# Omnitouch.net
KiCad netlist of a schematic drawn in EasyEDA
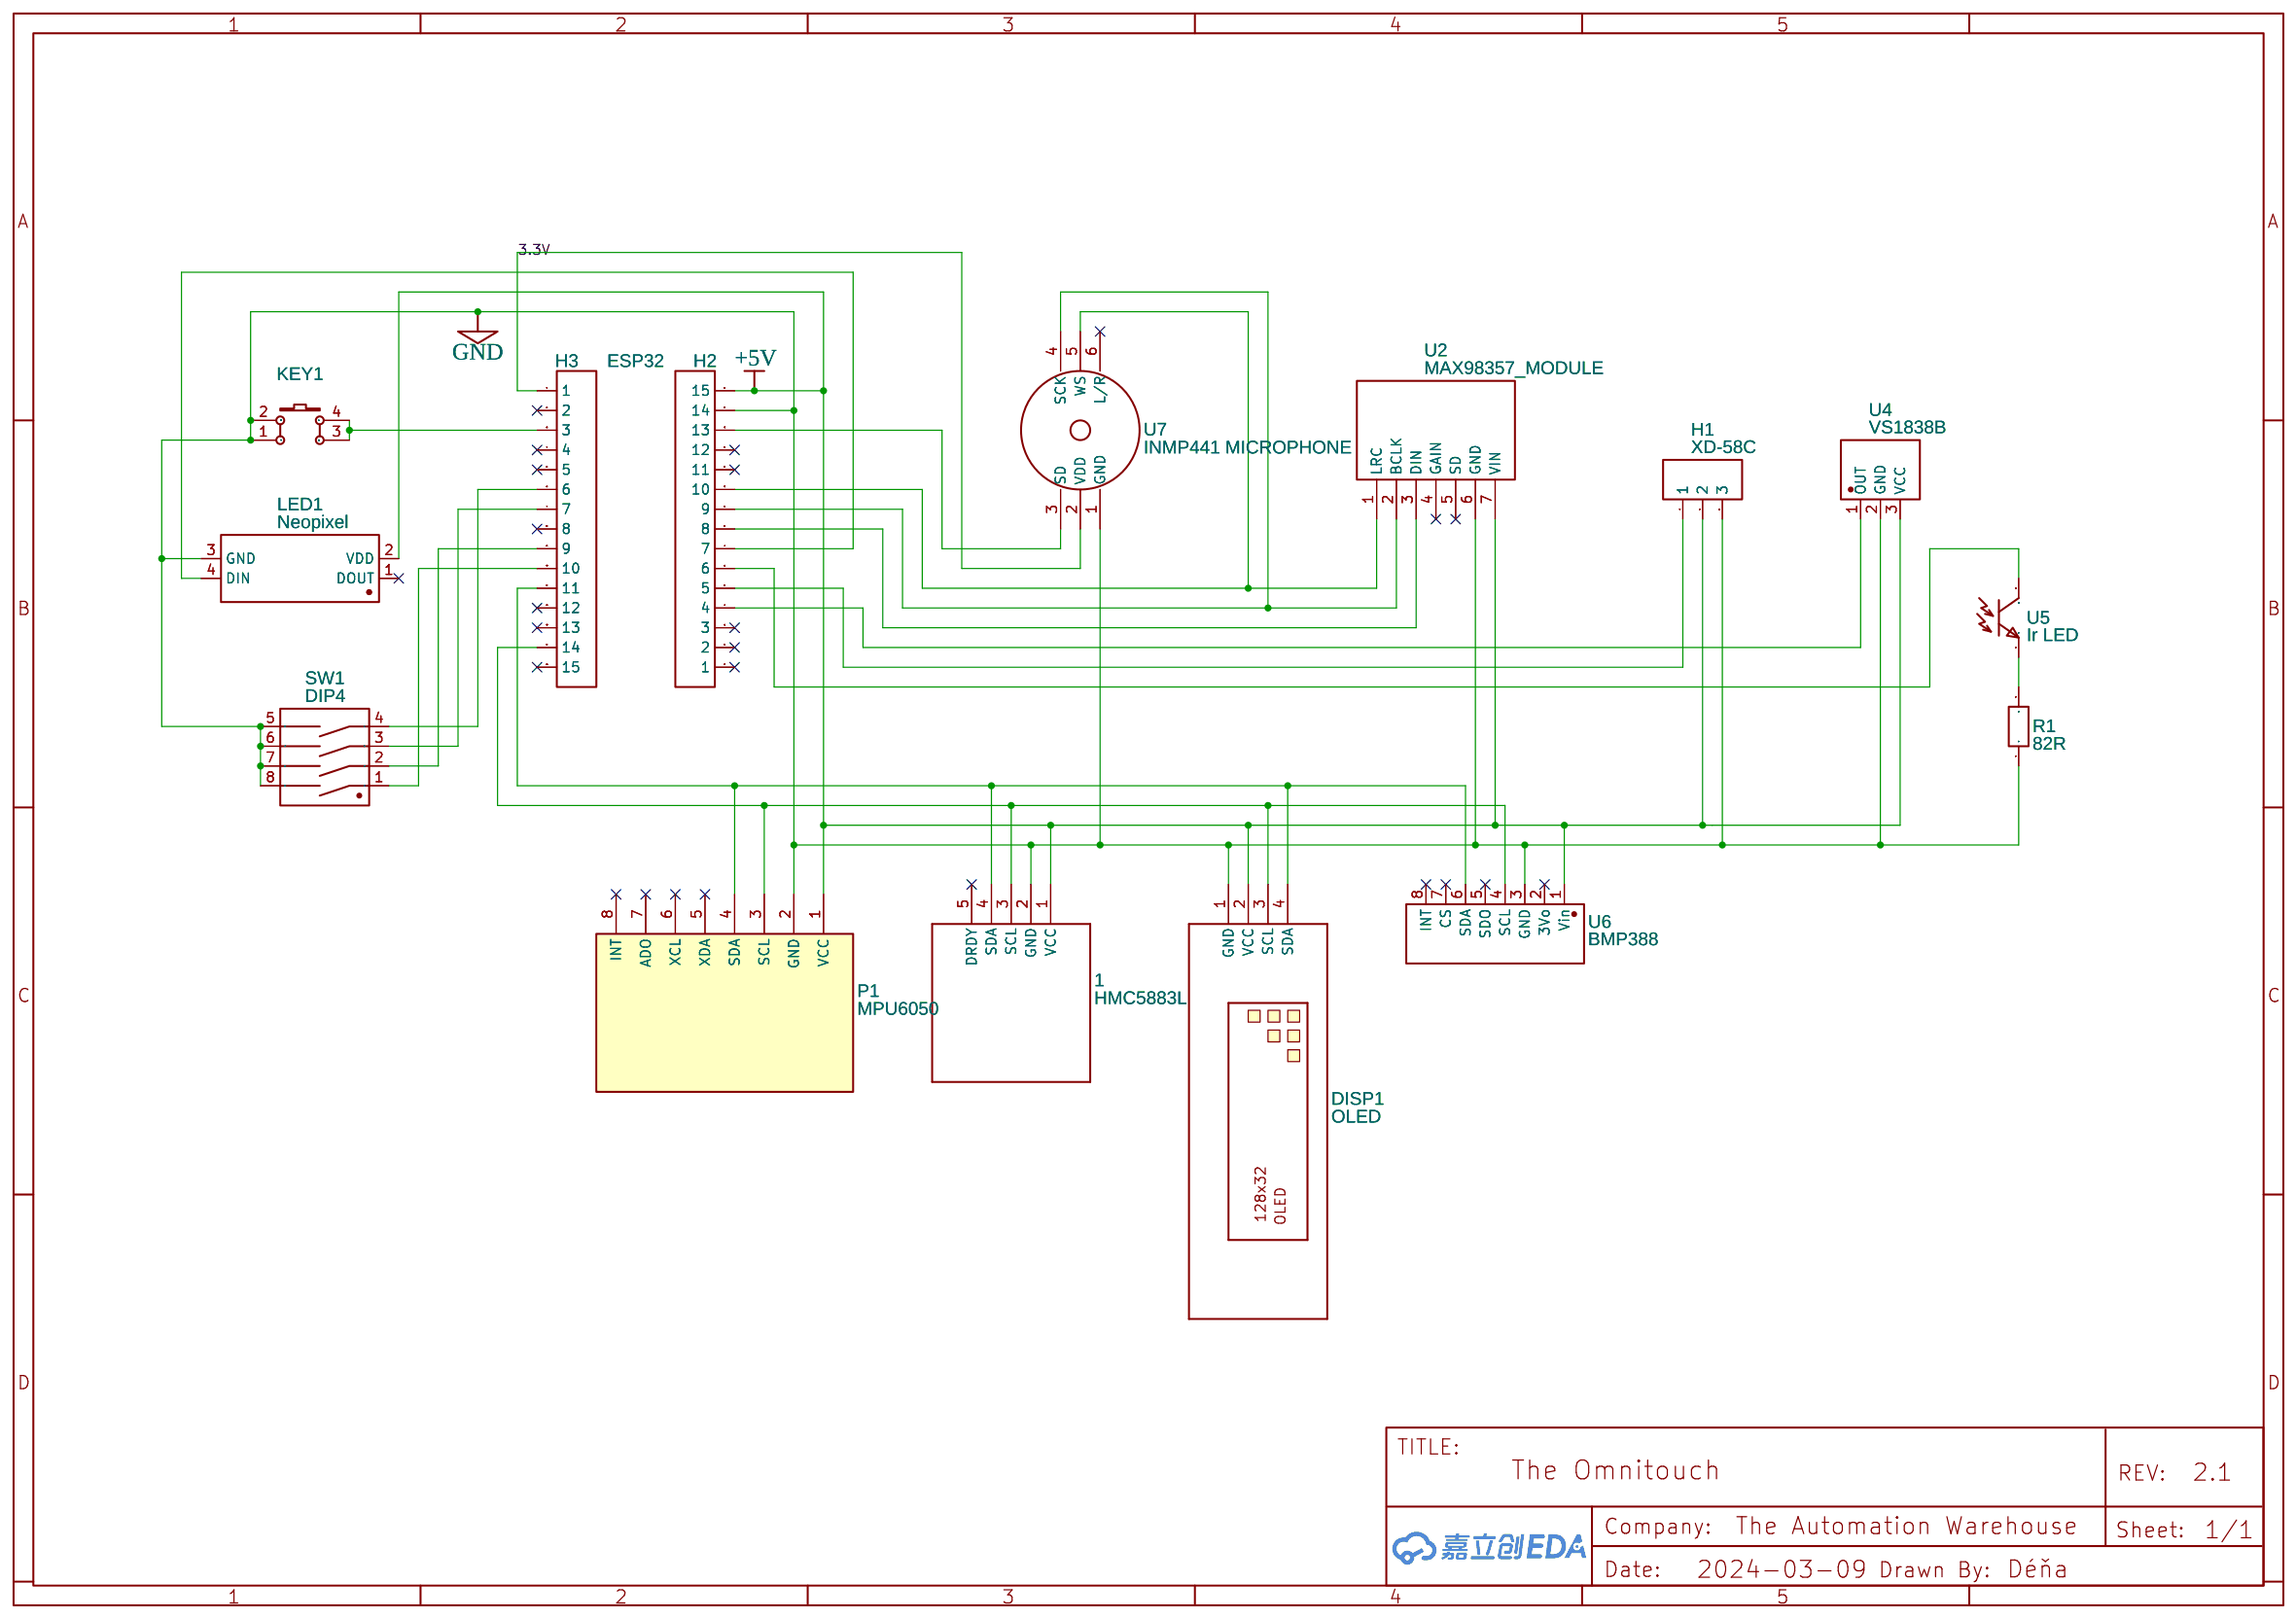
[diagram p0: schematic sheet]

(export (version "E")
  (design (tool "Eeschema 10.0.6"))
  (components
    (comp (ref "1") (value "HMC5883L") (libsource (lib "") (part "COMPASS-HMC5883L")))
    (comp (ref "DISP1") (value "OLED") (libsource (lib "") (part "DISPLAY-OLED-128X32")))
    (comp (ref "H1")
      (value "XD-58C")
      (fields (field (name "BOM_Supplier Part") "C146690"))
      (libsource (lib "") (part "HDR-F-2.54_1x3"))
    )
    (comp (ref "H2")
      (value "HDR-F-2.54_1x15")
      (fields (field (name "BOM_Supplier Part") "C124408"))
      (libsource (lib "") (part "HDR-F-2.54_1x15_1"))
    )
    (comp (ref "H3")
      (value "ESP32")
      (fields (field (name "BOM_Supplier Part") "C124408"))
      (libsource (lib "") (part "HDR-F-2.54_1x15"))
    )
    (comp (ref "KEY1")
      (value "K4-6×6_TH")
      (fields
        (field (name "BOM_Manufacturer Part") "K2-1102DP-E4SW-04")
        (field (name "BOM_Supplier Part") "C136684")
      )
      (libsource (lib "") (part "K4-6×6_TH"))
    )
    (comp (ref "LED1")
      (value "Neopixel")
      (fields (field (name "Manufacturer Part") "WS2812D-F8") (field (name "Manufacturer") "worldsemi"))
      (libsource (lib "") (part "WS2812D-F8"))
    )
    (comp (ref "P1") (value "MPU6050") (libsource (lib "") (part "MPU6050")))
    (comp (ref "R1") (value "82R") (libsource (lib "") (part "R_AXIAL-0.4_EU")))
    (comp (ref "SW1")
      (value "DIP4")
      (fields
        (field (name "Manufacturer Part") "KF1001-04P-R0-GL-DFT-01B")
        (field (name "Manufacturer") "凯峰")
      )
      (libsource (lib "") (part "KF1001-04P-R0-GL-DFT-01B"))
    )
    (comp (ref "U2")
      (value "MAX98357_MODULE")
      (fields (field (name "BOM_Manufacturer Part") "MAX98357"))
      (libsource (lib "") (part "MAX98357_MODULE"))
    )
    (comp (ref "U4") (value "VS1838B") (libsource (lib "") (part "VS1838B")))
    (comp (ref "U5")
      (value "Ir LED")
      (fields
        (field (name "Manufacturer Part") "PT334-6B(BY)(K)")
        (field (name "Manufacturer") "EVERLIGHT(亿光)")
      )
      (libsource (lib "") (part "PT334-6B(BY)(K)"))
    )
    (comp (ref "U6") (value "BMP388") (libsource (lib "") (part "Adafruit BMP388")))
    (comp (ref "U7") (value "INMP441 MICROPHONE") (libsource (lib "") (part "INMP441 MICROPHONE")))
  )
  (nets
    (net (code "1") (name "+5V") (class "Default")
      (node (ref "1") (pin "1") (pinfunction "VCC_1") (pintype "bidirectional"))
      (node (ref "DISP1") (pin "2") (pinfunction "VCC_2") (pintype "bidirectional"))
      (node (ref "H1") (pin "2") (pinfunction "2_2") (pintype "input"))
      (node (ref "H2") (pin "15") (pinfunction "15_15") (pintype "unspecified"))
      (node (ref "LED1") (pin "2") (pinfunction "VDD_2") (pintype "unspecified"))
      (node (ref "P1") (pin "1") (pinfunction "VCC_1") (pintype "unspecified"))
      (node (ref "U2") (pin "7") (pinfunction "VIN_7") (pintype "unspecified"))
      (node (ref "U4") (pin "3") (pinfunction "VCC_3") (pintype "unspecified"))
      (node (ref "U6") (pin "1") (pinfunction "Vin_1") (pintype "unspecified"))
    )
    (net (code "2") (name "/3.3V") (class "Default")
      (node (ref "H3") (pin "1") (pinfunction "1_1") (pintype "unspecified"))
      (node (ref "U7") (pin "2") (pinfunction "VDD_2") (pintype "unspecified"))
    )
    (net (code "3") (name "GND") (class "Default")
      (node (ref "1") (pin "2") (pinfunction "GND_2") (pintype "bidirectional"))
      (node (ref "DISP1") (pin "1") (pinfunction "GND_1") (pintype "bidirectional"))
      (node (ref "H1") (pin "3") (pinfunction "3_3") (pintype "input"))
      (node (ref "H2") (pin "14") (pinfunction "14_14") (pintype "unspecified"))
      (node (ref "KEY1") (pin "1") (pinfunction "1_1") (pintype "unspecified"))
      (node (ref "KEY1") (pin "2") (pinfunction "2_2") (pintype "unspecified"))
      (node (ref "LED1") (pin "3") (pinfunction "GND_3") (pintype "unspecified"))
      (node (ref "P1") (pin "2") (pinfunction "GND_2") (pintype "unspecified"))
      (node (ref "R1") (pin "1") (pinfunction "1_1") (pintype "unspecified"))
      (node (ref "SW1") (pin "5") (pinfunction "6_5") (pintype "unspecified"))
      (node (ref "SW1") (pin "6") (pinfunction "7_6") (pintype "unspecified"))
      (node (ref "SW1") (pin "7") (pinfunction "8_7") (pintype "unspecified"))
      (node (ref "SW1") (pin "8") (pinfunction "9_8") (pintype "unspecified"))
      (node (ref "U2") (pin "6") (pinfunction "GND_6") (pintype "unspecified"))
      (node (ref "U4") (pin "2") (pinfunction "GND_2") (pintype "unspecified"))
      (node (ref "U6") (pin "3") (pinfunction "GND_3") (pintype "unspecified"))
      (node (ref "U7") (pin "1") (pinfunction "GND_1") (pintype "unspecified"))
    )
    (net (code "4") (name "Net-(1-SCL)") (class "Default")
      (node (ref "1") (pin "3") (pinfunction "SCL_3") (pintype "bidirectional"))
      (node (ref "DISP1") (pin "3") (pinfunction "SCL_3") (pintype "bidirectional"))
      (node (ref "H3") (pin "14") (pinfunction "14_14") (pintype "unspecified"))
      (node (ref "P1") (pin "3") (pinfunction "SCL_3") (pintype "unspecified"))
      (node (ref "U6") (pin "4") (pinfunction "SCL_4") (pintype "unspecified"))
    )
    (net (code "5") (name "Net-(1-SDA)") (class "Default")
      (node (ref "1") (pin "4") (pinfunction "SDA_4") (pintype "bidirectional"))
      (node (ref "DISP1") (pin "4") (pinfunction "SDA_4") (pintype "bidirectional"))
      (node (ref "H3") (pin "11") (pinfunction "11_11") (pintype "unspecified"))
      (node (ref "P1") (pin "4") (pinfunction "SDA_4") (pintype "unspecified"))
      (node (ref "U6") (pin "6") (pinfunction "SDA_6") (pintype "unspecified"))
    )
    (net (code "6") (name "Net-(H1-Pad1)") (class "Default")
      (node (ref "H1") (pin "1") (pinfunction "1_1") (pintype "input"))
      (node (ref "H2") (pin "5") (pinfunction "5_5") (pintype "unspecified"))
    )
    (net (code "7") (name "Net-(H3-Pad3)") (class "Default")
      (node (ref "H3") (pin "3") (pinfunction "3_3") (pintype "unspecified"))
      (node (ref "KEY1") (pin "3") (pinfunction "3_3") (pintype "unspecified"))
      (node (ref "KEY1") (pin "4") (pinfunction "4_4") (pintype "unspecified"))
    )
    (net (code "8") (name "Net-(H3-Pad6)") (class "Default")
      (node (ref "H3") (pin "6") (pinfunction "6_6") (pintype "unspecified"))
      (node (ref "SW1") (pin "4") (pinfunction "4_4") (pintype "unspecified"))
    )
    (net (code "9") (name "Net-(H3-Pad7)") (class "Default")
      (node (ref "H3") (pin "7") (pinfunction "7_7") (pintype "unspecified"))
      (node (ref "SW1") (pin "3") (pinfunction "3_3") (pintype "unspecified"))
    )
    (net (code "10") (name "Net-(H3-Pad9)") (class "Default")
      (node (ref "H3") (pin "9") (pinfunction "9_9") (pintype "unspecified"))
      (node (ref "SW1") (pin "2") (pinfunction "2_2") (pintype "unspecified"))
    )
    (net (code "11") (name "Net-(H3-Pad10)") (class "Default")
      (node (ref "H3") (pin "10") (pinfunction "10_10") (pintype "unspecified"))
      (node (ref "SW1") (pin "1") (pinfunction "1_1") (pintype "unspecified"))
    )
    (net (code "12") (name "Net-(LED1-DIN)") (class "Default")
      (node (ref "H2") (pin "7") (pinfunction "7_7") (pintype "unspecified"))
      (node (ref "LED1") (pin "4") (pinfunction "DIN_4") (pintype "unspecified"))
    )
    (net (code "13") (name "Net-(U2-BCLK)") (class "Default")
      (node (ref "H2") (pin "9") (pinfunction "9_9") (pintype "unspecified"))
      (node (ref "U2") (pin "2") (pinfunction "BCLK_2") (pintype "unspecified"))
      (node (ref "U7") (pin "4") (pinfunction "SCK_4") (pintype "unspecified"))
    )
    (net (code "14") (name "Net-(U2-DIN)") (class "Default")
      (node (ref "H2") (pin "8") (pinfunction "8_8") (pintype "unspecified"))
      (node (ref "U2") (pin "3") (pinfunction "DIN_3") (pintype "unspecified"))
    )
    (net (code "15") (name "Net-(U2-LRC)") (class "Default")
      (node (ref "H2") (pin "10") (pinfunction "10_10") (pintype "unspecified"))
      (node (ref "U2") (pin "1") (pinfunction "LRC_1") (pintype "unspecified"))
      (node (ref "U7") (pin "5") (pinfunction "WS_5") (pintype "unspecified"))
    )
    (net (code "16") (name "Net-(U4-OUT)") (class "Default")
      (node (ref "H2") (pin "4") (pinfunction "4_4") (pintype "unspecified"))
      (node (ref "U4") (pin "1") (pinfunction "OUT_1") (pintype "unspecified"))
    )
    (net (code "17") (name "Net-(U5-C)") (class "Default")
      (node (ref "H2") (pin "6") (pinfunction "6_6") (pintype "unspecified"))
      (node (ref "U5") (pin "2") (pinfunction "C_2") (pintype "unspecified"))
    )
    (net (code "18") (name "Net-(U5-E)") (class "Default")
      (node (ref "R1") (pin "2") (pinfunction "2_2") (pintype "unspecified"))
      (node (ref "U5") (pin "1") (pinfunction "E_1") (pintype "unspecified"))
    )
    (net (code "19") (name "Net-(U7-SD)") (class "Default")
      (node (ref "H2") (pin "13") (pinfunction "13_13") (pintype "unspecified"))
      (node (ref "U7") (pin "3") (pinfunction "SD_3") (pintype "unspecified"))
    )
    (net (code "20") (name "unconnected-(1-DRDY-Pad5)") (class "Default")
      (node (ref "1") (pin "5") (pinfunction "DRDY_5") (pintype "bidirectional+no_connect"))
    )
    (net (code "21") (name "unconnected-(H2-Pad1)") (class "Default")
      (node (ref "H2") (pin "1") (pinfunction "1_1") (pintype "unspecified+no_connect"))
    )
    (net (code "22") (name "unconnected-(H2-Pad2)") (class "Default")
      (node (ref "H2") (pin "2") (pinfunction "2_2") (pintype "unspecified+no_connect"))
    )
    (net (code "23") (name "unconnected-(H2-Pad3)") (class "Default")
      (node (ref "H2") (pin "3") (pinfunction "3_3") (pintype "unspecified+no_connect"))
    )
    (net (code "24") (name "unconnected-(H2-Pad11)") (class "Default")
      (node (ref "H2") (pin "11") (pinfunction "11_11") (pintype "unspecified+no_connect"))
    )
    (net (code "25") (name "unconnected-(H2-Pad12)") (class "Default")
      (node (ref "H2") (pin "12") (pinfunction "12_12") (pintype "unspecified+no_connect"))
    )
    (net (code "26") (name "unconnected-(H3-Pad2)") (class "Default")
      (node (ref "H3") (pin "2") (pinfunction "2_2") (pintype "unspecified+no_connect"))
    )
    (net (code "27") (name "unconnected-(H3-Pad4)") (class "Default")
      (node (ref "H3") (pin "4") (pinfunction "4_4") (pintype "unspecified+no_connect"))
    )
    (net (code "28") (name "unconnected-(H3-Pad5)") (class "Default")
      (node (ref "H3") (pin "5") (pinfunction "5_5") (pintype "unspecified+no_connect"))
    )
    (net (code "29") (name "unconnected-(H3-Pad8)") (class "Default")
      (node (ref "H3") (pin "8") (pinfunction "8_8") (pintype "unspecified+no_connect"))
    )
    (net (code "30") (name "unconnected-(H3-Pad12)") (class "Default")
      (node (ref "H3") (pin "12") (pinfunction "12_12") (pintype "unspecified+no_connect"))
    )
    (net (code "31") (name "unconnected-(H3-Pad13)") (class "Default")
      (node (ref "H3") (pin "13") (pinfunction "13_13") (pintype "unspecified+no_connect"))
    )
    (net (code "32") (name "unconnected-(H3-Pad15)") (class "Default")
      (node (ref "H3") (pin "15") (pinfunction "15_15") (pintype "unspecified+no_connect"))
    )
    (net (code "33") (name "unconnected-(LED1-DOUT-Pad1)") (class "Default")
      (node (ref "LED1") (pin "1") (pinfunction "DOUT_1") (pintype "unspecified+no_connect"))
    )
    (net (code "34") (name "unconnected-(P1-ADO-Pad7)") (class "Default")
      (node (ref "P1") (pin "7") (pinfunction "ADO_7") (pintype "unspecified+no_connect"))
    )
    (net (code "35") (name "unconnected-(P1-INT-Pad8)") (class "Default")
      (node (ref "P1") (pin "8") (pinfunction "INT_8") (pintype "unspecified+no_connect"))
    )
    (net (code "36") (name "unconnected-(P1-XCL-Pad6)") (class "Default")
      (node (ref "P1") (pin "6") (pinfunction "XCL_6") (pintype "unspecified+no_connect"))
    )
    (net (code "37") (name "unconnected-(P1-XDA-Pad5)") (class "Default")
      (node (ref "P1") (pin "5") (pinfunction "XDA_5") (pintype "unspecified+no_connect"))
    )
    (net (code "38") (name "unconnected-(U2-GAIN-Pad4)") (class "Default")
      (node (ref "U2") (pin "4") (pinfunction "GAIN_4") (pintype "unspecified+no_connect"))
    )
    (net (code "39") (name "unconnected-(U2-SD-Pad5)") (class "Default")
      (node (ref "U2") (pin "5") (pinfunction "SD_5") (pintype "unspecified+no_connect"))
    )
    (net (code "40") (name "unconnected-(U6-3Vo-Pad2)") (class "Default")
      (node (ref "U6") (pin "2") (pinfunction "3Vo_2") (pintype "unspecified+no_connect"))
    )
    (net (code "41") (name "unconnected-(U6-CS-Pad7)") (class "Default")
      (node (ref "U6") (pin "7") (pinfunction "CS_7") (pintype "unspecified+no_connect"))
    )
    (net (code "42") (name "unconnected-(U6-INT-Pad8)") (class "Default")
      (node (ref "U6") (pin "8") (pinfunction "INT_8") (pintype "unspecified+no_connect"))
    )
    (net (code "43") (name "unconnected-(U6-SDO-Pad5)") (class "Default")
      (node (ref "U6") (pin "5") (pinfunction "SDO_5") (pintype "unspecified+no_connect"))
    )
    (net (code "44") (name "unconnected-(U7-L{slash}R-Pad6)") (class "Default")
      (node (ref "U7") (pin "6") (pinfunction "L/R_6") (pintype "unspecified+no_connect"))
    )
  )
)
